# XStepperLCD.net
KiCad netlist of a schematic drawn in EAGLE
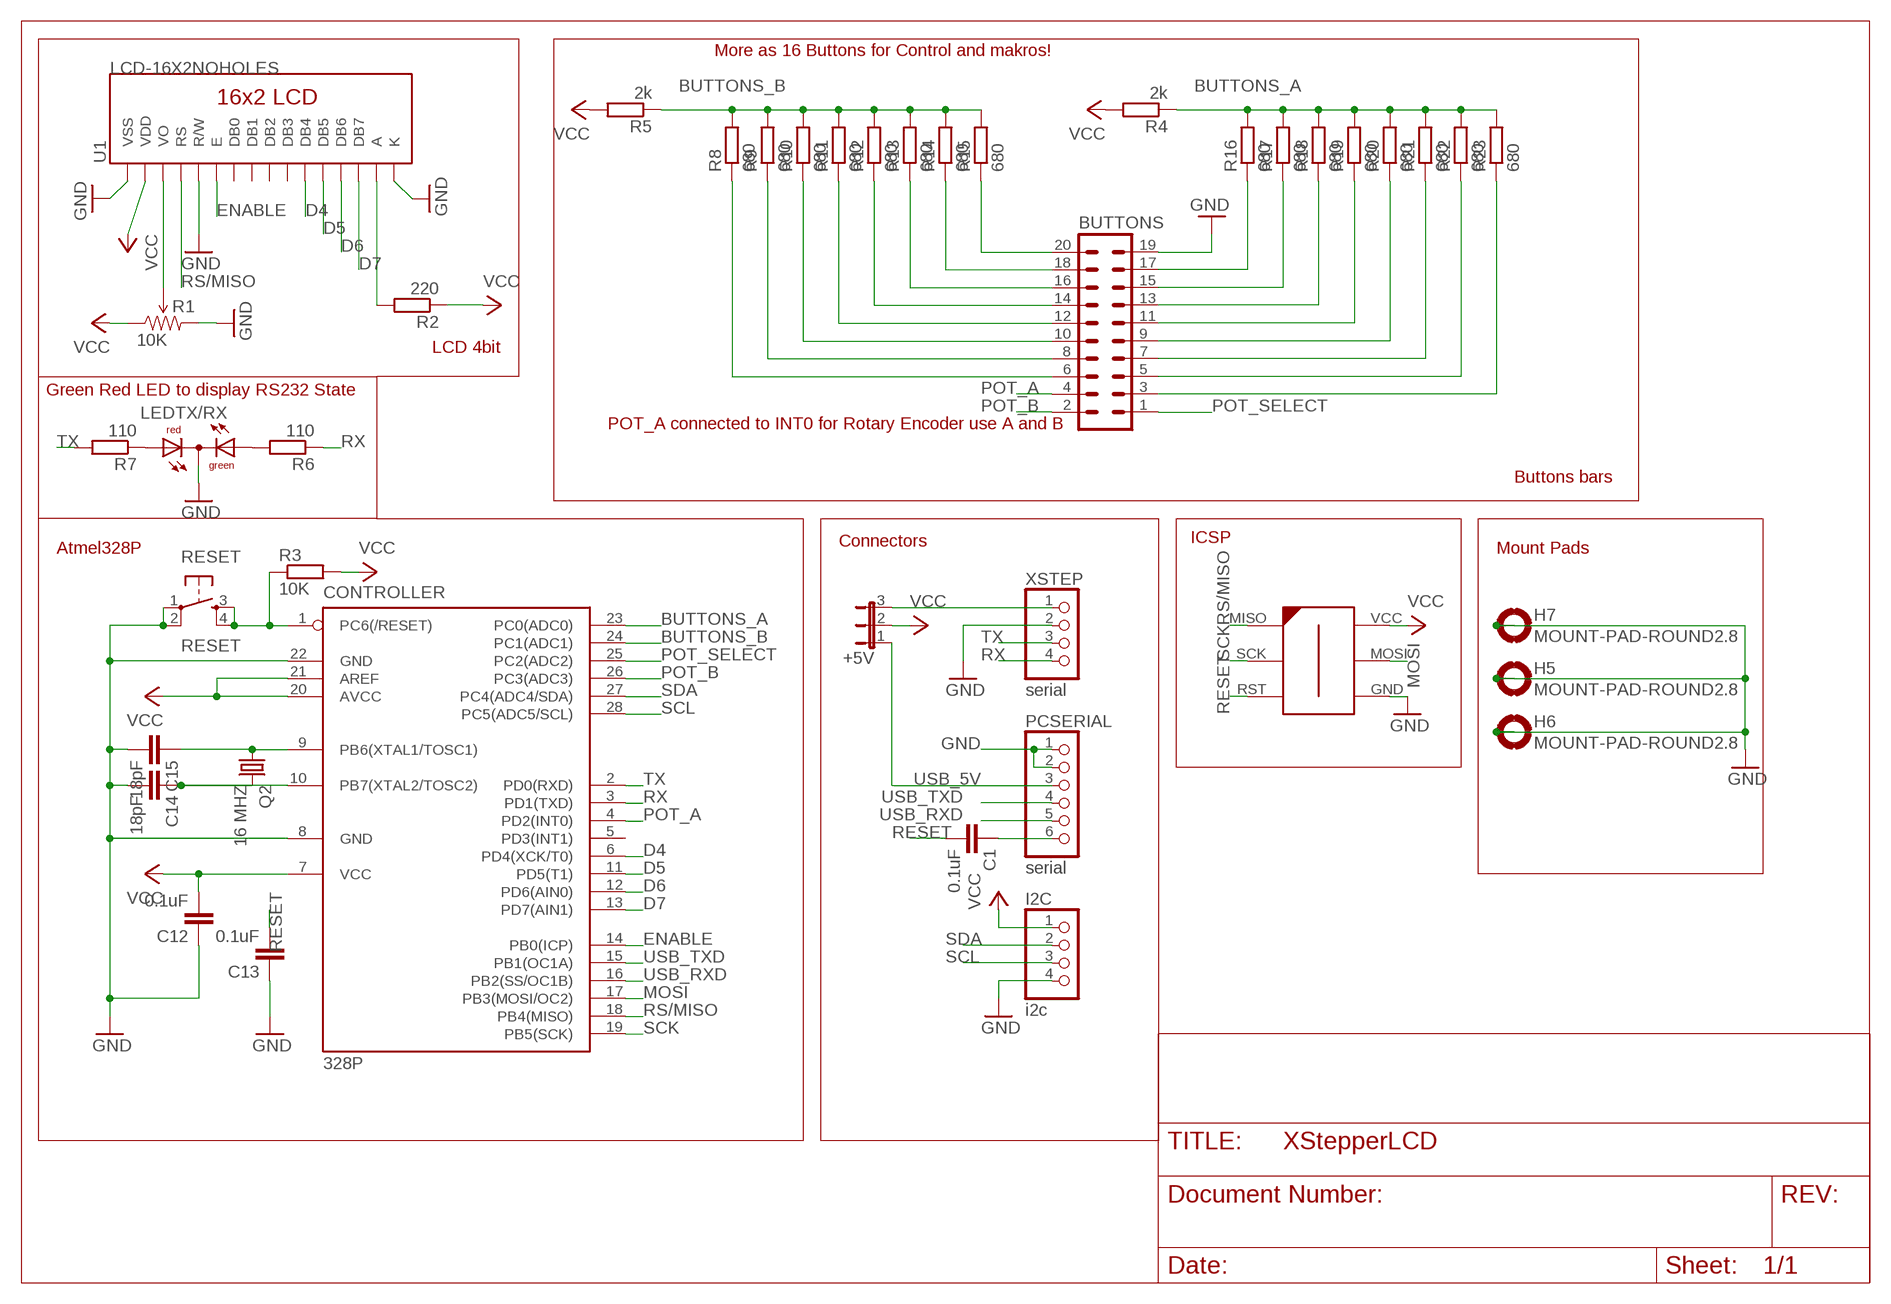
[diagram p0: schematic, sheet 1]

(export (version "E")
  (design (tool "Eeschema 10.0.6"))
  (components
    (comp (ref "+5V")
      (value "JP2E")
      (footprint "eagle-import:JP2")
      (libsource (lib "eagle-import") (part "JP2E"))
    )
    (comp (ref "328P")
      (value "CONTROLLER")
      (footprint "eagle-import:DIL28-3")
      (libsource (lib "eagle-import") (part "MEGA8-P"))
    )
    (comp (ref "BUTTONS")
      (value "ML20")
      (footprint "eagle-import:ML20")
      (libsource (lib "eagle-import") (part "ML20"))
    )
    (comp (ref "C1")
      (value "0.1uF")
      (footprint "eagle-import:C1206")
      (libsource (lib "eagle-import") (part "C-EUC1206"))
    )
    (comp (ref "C12")
      (value "0.1uF")
      (footprint "eagle-import:C1206K")
      (libsource (lib "eagle-import") (part "C-EUC1206K"))
    )
    (comp (ref "C13")
      (value "0.1uF")
      (footprint "eagle-import:C1206")
      (libsource (lib "eagle-import") (part "C-EUC1206"))
    )
    (comp (ref "C14")
      (value "18pF")
      (footprint "eagle-import:C025-025X050")
      (libsource (lib "eagle-import") (part "C-EU025-025X050"))
    )
    (comp (ref "C15")
      (value "18pF")
      (footprint "eagle-import:C025-025X050")
      (libsource (lib "eagle-import") (part "C-EU025-025X050"))
    )
    (comp (ref "H5")
      (value "MOUNT-PAD-ROUND2.8")
      (footprint "eagle-import:2,8-PAD")
      (libsource (lib "eagle-import") (part "MOUNT-PAD-ROUND2.8"))
    )
    (comp (ref "H6")
      (value "MOUNT-PAD-ROUND2.8")
      (footprint "eagle-import:2,8-PAD")
      (libsource (lib "eagle-import") (part "MOUNT-PAD-ROUND2.8"))
    )
    (comp (ref "H7")
      (value "MOUNT-PAD-ROUND2.8")
      (footprint "eagle-import:2,8-PAD")
      (libsource (lib "eagle-import") (part "MOUNT-PAD-ROUND2.8"))
    )
    (comp (ref "I2C")
      (value "i2c")
      (footprint "eagle-import:1X04_90")
      (libsource (lib "eagle-import") (part "PINHD-1X4/90"))
    )
    (comp (ref "ICSP")
      (value "ICSP")
      (footprint "eagle-import:6PAD_ISP")
      (libsource (lib "eagle-import") (part "AVR-ISP-6-EDGE"))
    )
    (comp (ref "LEDTX/RX")
      (value "DUOLED2X5")
      (footprint "eagle-import:DUOLED2X5")
      (libsource (lib "eagle-import") (part "DUOLED2X5"))
    )
    (comp (ref "PCSERIAL")
      (value "serial")
      (footprint "eagle-import:1X06_90")
      (libsource (lib "eagle-import") (part "PINHD-1X6/90"))
    )
    (comp (ref "Q2")
      (value "16 MHZ")
      (footprint "eagle-import:HC49_S")
      (libsource (lib "eagle-import") (part "CRYSTALHC49S"))
    )
    (comp (ref "R1")
      (value "10K")
      (footprint "eagle-import:3362U-2")
      (libsource (lib "eagle-import") (part "TRIMPOT3362U-2"))
    )
    (comp (ref "R2")
      (value "220")
      (footprint "eagle-import:R1206")
      (libsource (lib "eagle-import") (part "R-EU_R1206"))
    )
    (comp (ref "R3")
      (value "10K")
      (footprint "eagle-import:R1206")
      (libsource (lib "eagle-import") (part "R-EU_R1206"))
    )
    (comp (ref "R4")
      (value "2k")
      (footprint "eagle-import:R1206")
      (libsource (lib "eagle-import") (part "R-EU_R1206"))
    )
    (comp (ref "R5")
      (value "2k")
      (footprint "eagle-import:R1206")
      (libsource (lib "eagle-import") (part "R-EU_R1206"))
    )
    (comp (ref "R6")
      (value "110")
      (footprint "eagle-import:R1206")
      (libsource (lib "eagle-import") (part "R-EU_R1206"))
    )
    (comp (ref "R7")
      (value "110")
      (footprint "eagle-import:R1206")
      (libsource (lib "eagle-import") (part "R-EU_R1206"))
    )
    (comp (ref "R8")
      (value "680")
      (footprint "eagle-import:R1206")
      (libsource (lib "eagle-import") (part "R-EU_R1206"))
    )
    (comp (ref "R9")
      (value "680")
      (footprint "eagle-import:R1206")
      (libsource (lib "eagle-import") (part "R-EU_R1206"))
    )
    (comp (ref "R10")
      (value "680")
      (footprint "eagle-import:R1206")
      (libsource (lib "eagle-import") (part "R-EU_R1206"))
    )
    (comp (ref "R11")
      (value "680")
      (footprint "eagle-import:R1206")
      (libsource (lib "eagle-import") (part "R-EU_R1206"))
    )
    (comp (ref "R12")
      (value "680")
      (footprint "eagle-import:R1206")
      (libsource (lib "eagle-import") (part "R-EU_R1206"))
    )
    (comp (ref "R13")
      (value "680")
      (footprint "eagle-import:R1206")
      (libsource (lib "eagle-import") (part "R-EU_R1206"))
    )
    (comp (ref "R14")
      (value "680")
      (footprint "eagle-import:R1206")
      (libsource (lib "eagle-import") (part "R-EU_R1206"))
    )
    (comp (ref "R15")
      (value "680")
      (footprint "eagle-import:R1206")
      (libsource (lib "eagle-import") (part "R-EU_R1206"))
    )
    (comp (ref "R16")
      (value "680")
      (footprint "eagle-import:R1206")
      (libsource (lib "eagle-import") (part "R-EU_R1206"))
    )
    (comp (ref "R17")
      (value "680")
      (footprint "eagle-import:R1206")
      (libsource (lib "eagle-import") (part "R-EU_R1206"))
    )
    (comp (ref "R18")
      (value "680")
      (footprint "eagle-import:R1206")
      (libsource (lib "eagle-import") (part "R-EU_R1206"))
    )
    (comp (ref "R19")
      (value "680")
      (footprint "eagle-import:R1206")
      (libsource (lib "eagle-import") (part "R-EU_R1206"))
    )
    (comp (ref "R20")
      (value "680")
      (footprint "eagle-import:R1206")
      (libsource (lib "eagle-import") (part "R-EU_R1206"))
    )
    (comp (ref "R21")
      (value "680")
      (footprint "eagle-import:R1206")
      (libsource (lib "eagle-import") (part "R-EU_R1206"))
    )
    (comp (ref "R22")
      (value "680")
      (footprint "eagle-import:R1206")
      (libsource (lib "eagle-import") (part "R-EU_R1206"))
    )
    (comp (ref "R23")
      (value "680")
      (footprint "eagle-import:R1206")
      (libsource (lib "eagle-import") (part "R-EU_R1206"))
    )
    (comp (ref "RESET")
      (value "RESET")
      (footprint "eagle-import:TACTILE-PTH")
      (libsource (lib "eagle-import") (part "TAC_SWITCHPTH"))
    )
    (comp (ref "U1")
      (value "LCD-16X2NOHOLES")
      (footprint "eagle-import:LCD-16X2_NOHOLES")
      (libsource (lib "eagle-import") (part "LCD-16X2NOHOLES"))
    )
    (comp (ref "XSTEP")
      (value "serial")
      (footprint "eagle-import:1X04_90")
      (libsource (lib "eagle-import") (part "PINHD-1X4/90"))
    )
  )
  (nets
    (net (code "1") (name "/BUTTONS_A") (class "Default")
      (node (ref "328P") (pin "23") (pinfunction "PC0(ADC0)_23") (pintype "bidirectional"))
      (node (ref "R16") (pin "2") (pinfunction "2_2") (pintype "passive"))
      (node (ref "R17") (pin "2") (pinfunction "2_2") (pintype "passive"))
      (node (ref "R18") (pin "2") (pinfunction "2_2") (pintype "passive"))
      (node (ref "R19") (pin "2") (pinfunction "2_2") (pintype "passive"))
      (node (ref "R20") (pin "2") (pinfunction "2_2") (pintype "passive"))
      (node (ref "R21") (pin "2") (pinfunction "2_2") (pintype "passive"))
      (node (ref "R22") (pin "2") (pinfunction "2_2") (pintype "passive"))
      (node (ref "R23") (pin "2") (pinfunction "2_2") (pintype "passive"))
      (node (ref "R4") (pin "1") (pinfunction "1_1") (pintype "passive"))
    )
    (net (code "2") (name "/BUTTONS_B") (class "Default")
      (node (ref "328P") (pin "24") (pinfunction "PC1(ADC1)_24") (pintype "bidirectional"))
      (node (ref "R10") (pin "2") (pinfunction "2_2") (pintype "passive"))
      (node (ref "R11") (pin "2") (pinfunction "2_2") (pintype "passive"))
      (node (ref "R12") (pin "2") (pinfunction "2_2") (pintype "passive"))
      (node (ref "R13") (pin "2") (pinfunction "2_2") (pintype "passive"))
      (node (ref "R14") (pin "2") (pinfunction "2_2") (pintype "passive"))
      (node (ref "R15") (pin "2") (pinfunction "2_2") (pintype "passive"))
      (node (ref "R5") (pin "1") (pinfunction "1_1") (pintype "passive"))
      (node (ref "R8") (pin "2") (pinfunction "2_2") (pintype "passive"))
      (node (ref "R9") (pin "2") (pinfunction "2_2") (pintype "passive"))
    )
    (net (code "3") (name "/D4") (class "Default")
      (node (ref "328P") (pin "6") (pinfunction "PD4(XCK/T0)_6") (pintype "bidirectional"))
      (node (ref "U1") (pin "11") (pinfunction "DB4_11") (pintype "bidirectional"))
    )
    (net (code "4") (name "/D5") (class "Default")
      (node (ref "328P") (pin "11") (pinfunction "PD5(T1)_11") (pintype "bidirectional"))
      (node (ref "U1") (pin "12") (pinfunction "DB5_12") (pintype "bidirectional"))
    )
    (net (code "5") (name "/D6") (class "Default")
      (node (ref "328P") (pin "12") (pinfunction "PD6(AIN0)_12") (pintype "bidirectional"))
      (node (ref "U1") (pin "13") (pinfunction "DB6_13") (pintype "bidirectional"))
    )
    (net (code "6") (name "/D7") (class "Default")
      (node (ref "328P") (pin "13") (pinfunction "PD7(AIN1)_13") (pintype "bidirectional"))
      (node (ref "U1") (pin "14") (pinfunction "DB7_14") (pintype "bidirectional"))
    )
    (net (code "7") (name "/ENABLE") (class "Default")
      (node (ref "328P") (pin "14") (pinfunction "PB0(ICP)_14") (pintype "bidirectional"))
      (node (ref "U1") (pin "6") (pinfunction "E_6") (pintype "input"))
    )
    (net (code "8") (name "/MOSI") (class "Default")
      (node (ref "328P") (pin "17") (pinfunction "PB3(MOSI/OC2)_17") (pintype "bidirectional"))
      (node (ref "ICSP") (pin "MOSI") (pinfunction "P$5_MOSI") (pintype "bidirectional"))
    )
    (net (code "9") (name "/POT_A") (class "Default")
      (node (ref "328P") (pin "4") (pinfunction "PD2(INT0)_4") (pintype "bidirectional"))
      (node (ref "BUTTONS") (pin "4") (pinfunction "4_4") (pintype "passive"))
    )
    (net (code "10") (name "/POT_B") (class "Default")
      (node (ref "328P") (pin "26") (pinfunction "PC3(ADC3)_26") (pintype "bidirectional"))
      (node (ref "BUTTONS") (pin "2") (pinfunction "2_2") (pintype "passive"))
    )
    (net (code "11") (name "/POT_SELECT") (class "Default")
      (node (ref "328P") (pin "25") (pinfunction "PC2(ADC2)_25") (pintype "bidirectional"))
      (node (ref "BUTTONS") (pin "1") (pinfunction "1_1") (pintype "passive"))
    )
    (net (code "12") (name "/RESET") (class "Default")
      (node (ref "328P") (pin "1") (pinfunction "PC6(/RESET)_1") (pintype "bidirectional"))
      (node (ref "C1") (pin "2") (pinfunction "2_2") (pintype "passive"))
      (node (ref "C13") (pin "2") (pinfunction "2_2") (pintype "passive"))
      (node (ref "ICSP") (pin "RST") (pinfunction "P$3_RST") (pintype "bidirectional"))
      (node (ref "R3") (pin "1") (pinfunction "1_1") (pintype "passive"))
      (node (ref "RESET") (pin "3") (pinfunction "3_3") (pintype "passive"))
      (node (ref "RESET") (pin "4") (pinfunction "4_4") (pintype "passive"))
    )
    (net (code "13") (name "/RS{slash}MISO") (class "Default")
      (node (ref "328P") (pin "18") (pinfunction "PB4(MISO)_18") (pintype "bidirectional"))
      (node (ref "ICSP") (pin "MISO") (pinfunction "P$1_MISO") (pintype "bidirectional"))
      (node (ref "U1") (pin "4") (pinfunction "RS_4") (pintype "input"))
    )
    (net (code "14") (name "/RX") (class "Default")
      (node (ref "328P") (pin "3") (pinfunction "PD1(TXD)_3") (pintype "bidirectional"))
      (node (ref "R6") (pin "1") (pinfunction "1_1") (pintype "passive"))
      (node (ref "XSTEP") (pin "4") (pinfunction "4_4") (pintype "passive"))
    )
    (net (code "15") (name "/SCK") (class "Default")
      (node (ref "328P") (pin "19") (pinfunction "PB5(SCK)_19") (pintype "bidirectional"))
      (node (ref "ICSP") (pin "SCK") (pinfunction "P$2_SCK") (pintype "bidirectional"))
    )
    (net (code "16") (name "/SCL") (class "Default")
      (node (ref "328P") (pin "28") (pinfunction "PC5(ADC5/SCL)_28") (pintype "bidirectional"))
      (node (ref "I2C") (pin "3") (pinfunction "3_3") (pintype "passive"))
    )
    (net (code "17") (name "/SDA") (class "Default")
      (node (ref "328P") (pin "27") (pinfunction "PC4(ADC4/SDA)_27") (pintype "bidirectional"))
      (node (ref "I2C") (pin "2") (pinfunction "2_2") (pintype "passive"))
    )
    (net (code "18") (name "/TX") (class "Default")
      (node (ref "328P") (pin "2") (pinfunction "PD0(RXD)_2") (pintype "bidirectional"))
      (node (ref "R7") (pin "2") (pinfunction "2_2") (pintype "passive"))
      (node (ref "XSTEP") (pin "3") (pinfunction "3_3") (pintype "passive"))
    )
    (net (code "19") (name "/USB_5V") (class "Default")
      (node (ref "+5V") (pin "1") (pinfunction "1_1") (pintype "passive"))
      (node (ref "PCSERIAL") (pin "3") (pinfunction "3_3") (pintype "passive"))
    )
    (net (code "20") (name "/USB_RXD") (class "Default")
      (node (ref "328P") (pin "16") (pinfunction "PB2(SS/OC1B)_16") (pintype "bidirectional"))
      (node (ref "PCSERIAL") (pin "5") (pinfunction "5_5") (pintype "passive"))
    )
    (net (code "21") (name "/USB_TXD") (class "Default")
      (node (ref "328P") (pin "15") (pinfunction "PB1(OC1A)_15") (pintype "bidirectional"))
      (node (ref "PCSERIAL") (pin "4") (pinfunction "4_4") (pintype "passive"))
    )
    (net (code "22") (name "GND") (class "Default")
      (node (ref "328P") (pin "22") (pinfunction "GND_22") (pintype "power_in"))
      (node (ref "328P") (pin "8") (pinfunction "GND_8") (pintype "power_in"))
      (node (ref "BUTTONS") (pin "19") (pinfunction "19_19") (pintype "passive"))
      (node (ref "C12") (pin "1") (pinfunction "1_1") (pintype "passive"))
      (node (ref "C13") (pin "1") (pinfunction "1_1") (pintype "passive"))
      (node (ref "C14") (pin "2") (pinfunction "2_2") (pintype "passive"))
      (node (ref "C15") (pin "2") (pinfunction "2_2") (pintype "passive"))
      (node (ref "H5") (pin "B2,8") (pinfunction "MOUNT_B2,8") (pintype "passive"))
      (node (ref "H6") (pin "B2,8") (pinfunction "MOUNT_B2,8") (pintype "passive"))
      (node (ref "H7") (pin "B2,8") (pinfunction "MOUNT_B2,8") (pintype "passive"))
      (node (ref "I2C") (pin "4") (pinfunction "4_4") (pintype "passive"))
      (node (ref "ICSP") (pin "GND") (pinfunction "P$4_GND") (pintype "bidirectional"))
      (node (ref "LEDTX/RX") (pin "K") (pinfunction "C_K") (pintype "passive"))
      (node (ref "PCSERIAL") (pin "1") (pinfunction "1_1") (pintype "passive"))
      (node (ref "PCSERIAL") (pin "2") (pinfunction "2_2") (pintype "passive"))
      (node (ref "R1") (pin "3") (pinfunction "CW_3") (pintype "passive"))
      (node (ref "RESET") (pin "1") (pinfunction "1_1") (pintype "passive"))
      (node (ref "RESET") (pin "2") (pinfunction "2_2") (pintype "passive"))
      (node (ref "U1") (pin "1") (pinfunction "VSS_1") (pintype "power_in"))
      (node (ref "U1") (pin "16") (pinfunction "K_16") (pintype "power_in"))
      (node (ref "U1") (pin "5") (pinfunction "R/W_5") (pintype "input"))
      (node (ref "XSTEP") (pin "2") (pinfunction "2_2") (pintype "passive"))
    )
    (net (code "23") (name "Net-(+5V-Pad3)") (class "Default")
      (node (ref "+5V") (pin "3") (pinfunction "3_3") (pintype "passive"))
      (node (ref "XSTEP") (pin "1") (pinfunction "1_1") (pintype "passive"))
    )
    (net (code "24") (name "Net-(328P-PB6(XTAL1{slash}TOSC1))") (class "Default")
      (node (ref "328P") (pin "9") (pinfunction "PB6(XTAL1/TOSC1)_9") (pintype "bidirectional"))
      (node (ref "C15") (pin "1") (pinfunction "1_1") (pintype "passive"))
      (node (ref "Q2") (pin "1") (pinfunction "1_1") (pintype "passive"))
    )
    (net (code "25") (name "Net-(328P-PB7(XTAL2{slash}TOSC2))") (class "Default")
      (node (ref "328P") (pin "10") (pinfunction "PB7(XTAL2/TOSC2)_10") (pintype "bidirectional"))
      (node (ref "C14") (pin "1") (pinfunction "1_1") (pintype "passive"))
      (node (ref "Q2") (pin "2") (pinfunction "2_2") (pintype "passive"))
    )
    (net (code "26") (name "Net-(BUTTONS-Pad3)") (class "Default")
      (node (ref "BUTTONS") (pin "3") (pinfunction "3_3") (pintype "passive"))
      (node (ref "R23") (pin "1") (pinfunction "1_1") (pintype "passive"))
    )
    (net (code "27") (name "Net-(BUTTONS-Pad5)") (class "Default")
      (node (ref "BUTTONS") (pin "5") (pinfunction "5_5") (pintype "passive"))
      (node (ref "R22") (pin "1") (pinfunction "1_1") (pintype "passive"))
    )
    (net (code "28") (name "Net-(BUTTONS-Pad6)") (class "Default")
      (node (ref "BUTTONS") (pin "6") (pinfunction "6_6") (pintype "passive"))
      (node (ref "R8") (pin "1") (pinfunction "1_1") (pintype "passive"))
    )
    (net (code "29") (name "Net-(BUTTONS-Pad7)") (class "Default")
      (node (ref "BUTTONS") (pin "7") (pinfunction "7_7") (pintype "passive"))
      (node (ref "R21") (pin "1") (pinfunction "1_1") (pintype "passive"))
    )
    (net (code "30") (name "Net-(BUTTONS-Pad8)") (class "Default")
      (node (ref "BUTTONS") (pin "8") (pinfunction "8_8") (pintype "passive"))
      (node (ref "R9") (pin "1") (pinfunction "1_1") (pintype "passive"))
    )
    (net (code "31") (name "Net-(BUTTONS-Pad9)") (class "Default")
      (node (ref "BUTTONS") (pin "9") (pinfunction "9_9") (pintype "passive"))
      (node (ref "R20") (pin "1") (pinfunction "1_1") (pintype "passive"))
    )
    (net (code "32") (name "Net-(BUTTONS-Pad10)") (class "Default")
      (node (ref "BUTTONS") (pin "10") (pinfunction "10_10") (pintype "passive"))
      (node (ref "R10") (pin "1") (pinfunction "1_1") (pintype "passive"))
    )
    (net (code "33") (name "Net-(BUTTONS-Pad11)") (class "Default")
      (node (ref "BUTTONS") (pin "11") (pinfunction "11_11") (pintype "passive"))
      (node (ref "R19") (pin "1") (pinfunction "1_1") (pintype "passive"))
    )
    (net (code "34") (name "Net-(BUTTONS-Pad12)") (class "Default")
      (node (ref "BUTTONS") (pin "12") (pinfunction "12_12") (pintype "passive"))
      (node (ref "R11") (pin "1") (pinfunction "1_1") (pintype "passive"))
    )
    (net (code "35") (name "Net-(BUTTONS-Pad13)") (class "Default")
      (node (ref "BUTTONS") (pin "13") (pinfunction "13_13") (pintype "passive"))
      (node (ref "R18") (pin "1") (pinfunction "1_1") (pintype "passive"))
    )
    (net (code "36") (name "Net-(BUTTONS-Pad14)") (class "Default")
      (node (ref "BUTTONS") (pin "14") (pinfunction "14_14") (pintype "passive"))
      (node (ref "R12") (pin "1") (pinfunction "1_1") (pintype "passive"))
    )
    (net (code "37") (name "Net-(BUTTONS-Pad15)") (class "Default")
      (node (ref "BUTTONS") (pin "15") (pinfunction "15_15") (pintype "passive"))
      (node (ref "R17") (pin "1") (pinfunction "1_1") (pintype "passive"))
    )
    (net (code "38") (name "Net-(BUTTONS-Pad16)") (class "Default")
      (node (ref "BUTTONS") (pin "16") (pinfunction "16_16") (pintype "passive"))
      (node (ref "R13") (pin "1") (pinfunction "1_1") (pintype "passive"))
    )
    (net (code "39") (name "Net-(BUTTONS-Pad17)") (class "Default")
      (node (ref "BUTTONS") (pin "17") (pinfunction "17_17") (pintype "passive"))
      (node (ref "R16") (pin "1") (pinfunction "1_1") (pintype "passive"))
    )
    (net (code "40") (name "Net-(BUTTONS-Pad18)") (class "Default")
      (node (ref "BUTTONS") (pin "18") (pinfunction "18_18") (pintype "passive"))
      (node (ref "R14") (pin "1") (pinfunction "1_1") (pintype "passive"))
    )
    (net (code "41") (name "Net-(BUTTONS-Pad20)") (class "Default")
      (node (ref "BUTTONS") (pin "20") (pinfunction "20_20") (pintype "passive"))
      (node (ref "R15") (pin "1") (pinfunction "1_1") (pintype "passive"))
    )
    (net (code "42") (name "Net-(C1-Pad1)") (class "Default")
      (node (ref "C1") (pin "1") (pinfunction "1_1") (pintype "passive"))
      (node (ref "PCSERIAL") (pin "6") (pinfunction "6_6") (pintype "passive"))
    )
    (net (code "43") (name "Net-(LEDTX/RX-PadAG)") (class "Default")
      (node (ref "LEDTX/RX") (pin "AG") (pinfunction "AG_AG") (pintype "passive"))
      (node (ref "R6") (pin "2") (pinfunction "2_2") (pintype "passive"))
    )
    (net (code "44") (name "Net-(LEDTX/RX-PadAR)") (class "Default")
      (node (ref "LEDTX/RX") (pin "AR") (pinfunction "AR_AR") (pintype "passive"))
      (node (ref "R7") (pin "1") (pinfunction "1_1") (pintype "passive"))
    )
    (net (code "45") (name "Net-(R1-WIPER)") (class "Default")
      (node (ref "R1") (pin "2") (pinfunction "WIPER_2") (pintype "passive"))
      (node (ref "U1") (pin "3") (pinfunction "VO_3") (pintype "bidirectional"))
    )
    (net (code "46") (name "Net-(U1-A)") (class "Default")
      (node (ref "R2") (pin "2") (pinfunction "2_2") (pintype "passive"))
      (node (ref "U1") (pin "15") (pinfunction "A_15") (pintype "power_in"))
    )
    (net (code "47") (name "VCC") (class "Default")
      (node (ref "+5V") (pin "2") (pinfunction "2_2") (pintype "passive"))
      (node (ref "328P") (pin "20") (pinfunction "AVCC_20") (pintype "power_in"))
      (node (ref "328P") (pin "21") (pinfunction "AREF_21") (pintype "passive"))
      (node (ref "328P") (pin "7") (pinfunction "VCC_7") (pintype "power_in"))
      (node (ref "C12") (pin "2") (pinfunction "2_2") (pintype "passive"))
      (node (ref "I2C") (pin "1") (pinfunction "1_1") (pintype "passive"))
      (node (ref "ICSP") (pin "VCC") (pinfunction "P$6_VCC") (pintype "bidirectional"))
      (node (ref "R1") (pin "1") (pinfunction "CCW_1") (pintype "passive"))
      (node (ref "R2") (pin "1") (pinfunction "1_1") (pintype "passive"))
      (node (ref "R3") (pin "2") (pinfunction "2_2") (pintype "passive"))
      (node (ref "R4") (pin "2") (pinfunction "2_2") (pintype "passive"))
      (node (ref "R5") (pin "2") (pinfunction "2_2") (pintype "passive"))
      (node (ref "U1") (pin "2") (pinfunction "VDD_2") (pintype "power_in"))
    )
    (net (code "48") (name "unconnected-(328P-PD3(INT1)-Pad5)") (class "Default")
      (node (ref "328P") (pin "5") (pinfunction "PD3(INT1)_5") (pintype "bidirectional"))
    )
    (net (code "49") (name "unconnected-(U1-DB0-Pad7)") (class "Default")
      (node (ref "U1") (pin "7") (pinfunction "DB0_7") (pintype "bidirectional"))
    )
    (net (code "50") (name "unconnected-(U1-DB1-Pad8)") (class "Default")
      (node (ref "U1") (pin "8") (pinfunction "DB1_8") (pintype "bidirectional"))
    )
    (net (code "51") (name "unconnected-(U1-DB2-Pad9)") (class "Default")
      (node (ref "U1") (pin "9") (pinfunction "DB2_9") (pintype "bidirectional"))
    )
    (net (code "52") (name "unconnected-(U1-DB3-Pad10)") (class "Default")
      (node (ref "U1") (pin "10") (pinfunction "DB3_10") (pintype "bidirectional"))
    )
  )
)
